# GaggiaBoard_V1.net
KiCad netlist of a schematic drawn in EAGLE
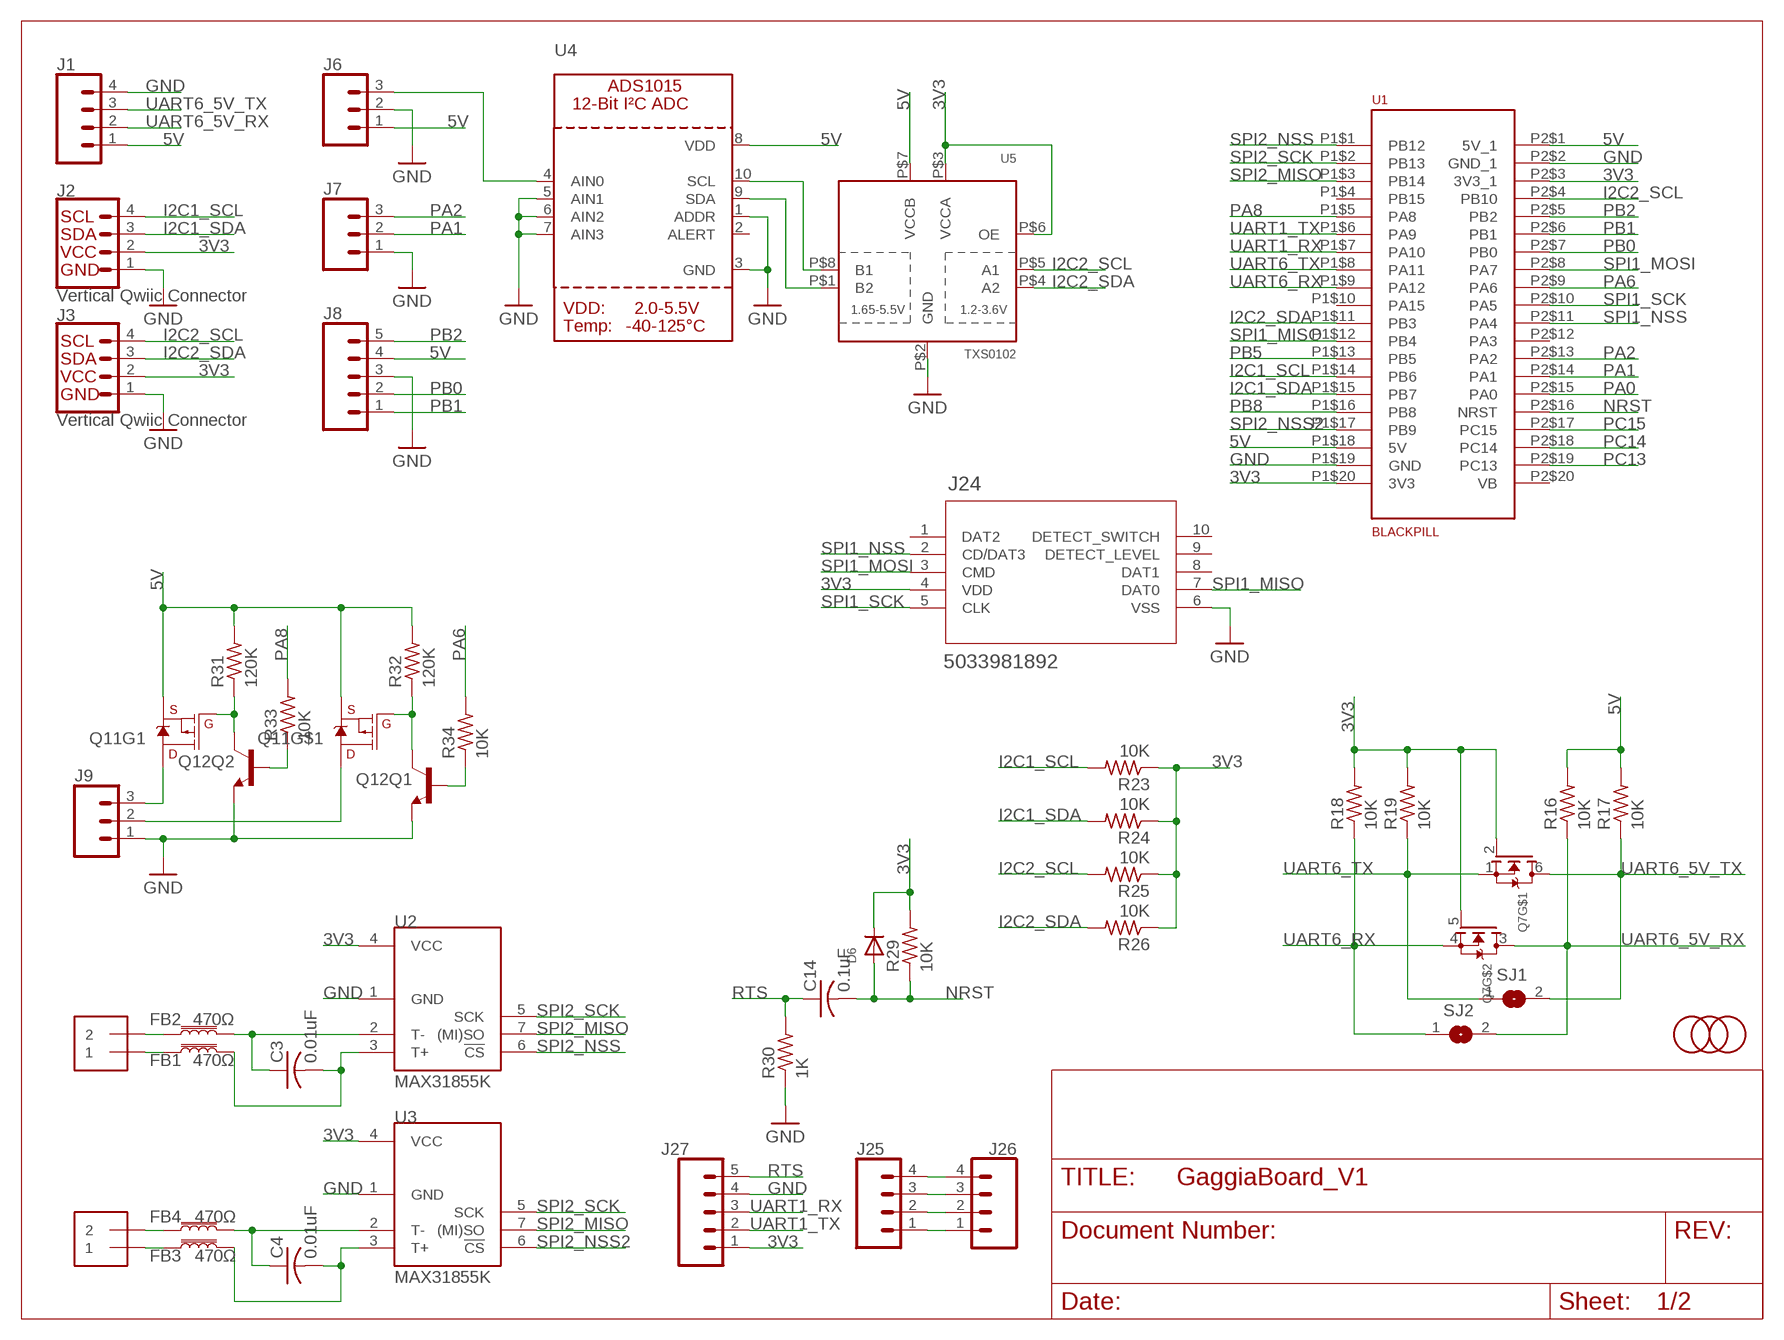
[diagram p0: schematic, sheet 1]
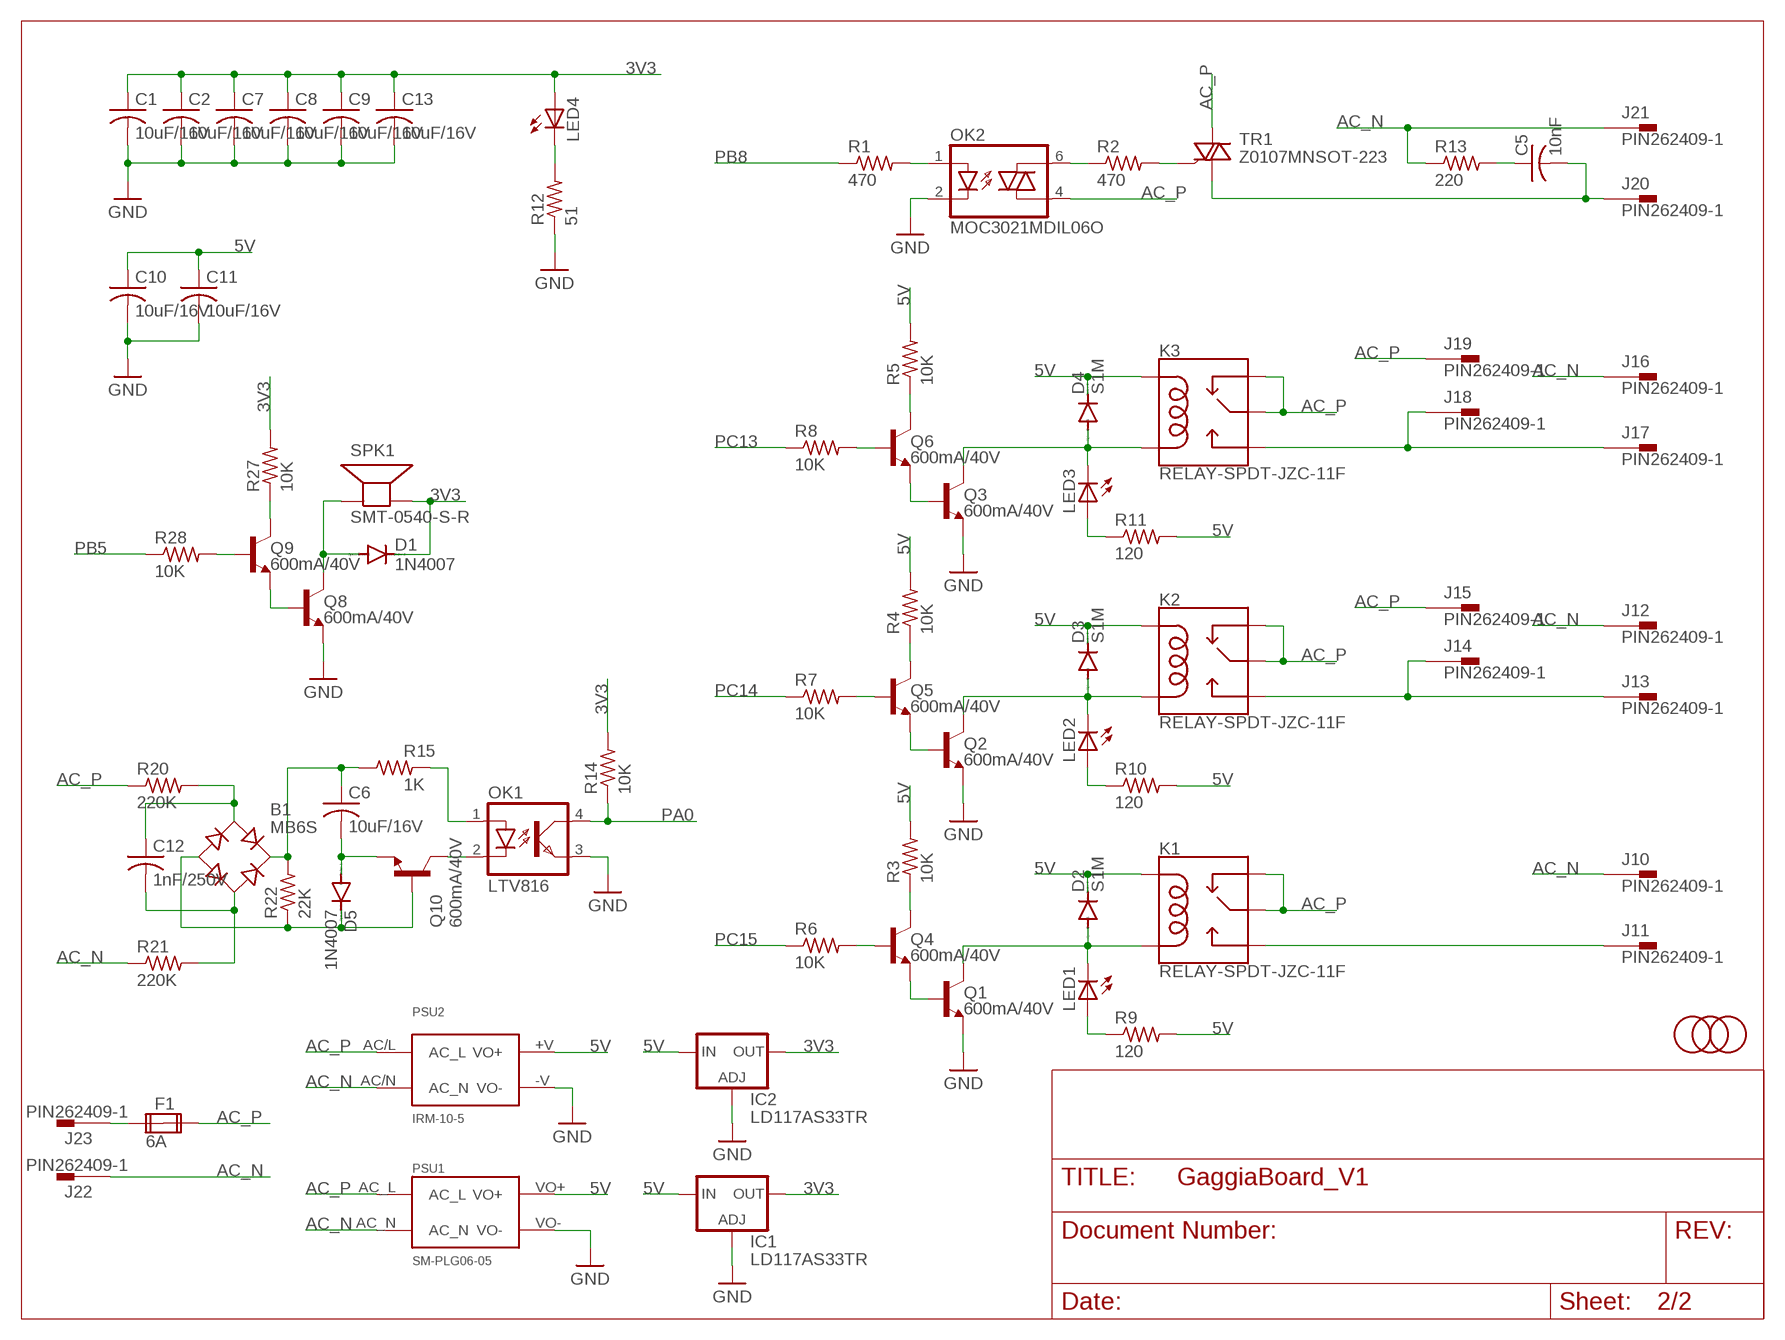
[diagram p1: schematic, sheet 2]

(export (version "E")
  (design (tool "Eeschema 10.0.6"))
  (components
    (comp (ref "B1")
      (value "MB6S")
      (footprint "eagle-import:SOIC-4")
      (libsource (lib "eagle-import") (part "MBS6"))
    )
    (comp (ref "C1")
      (value "10uF/16V")
      (footprint "eagle-import:C0603")
      (libsource (lib "eagle-import") (part "C-USC0603"))
    )
    (comp (ref "C2")
      (value "10uF/16V")
      (footprint "eagle-import:C0603")
      (libsource (lib "eagle-import") (part "C-USC0603"))
    )
    (comp (ref "C5")
      (value "10nF")
      (footprint "eagle-import:C1206")
      (libsource (lib "eagle-import") (part "C-USC1206"))
    )
    (comp (ref "C6")
      (value "10uF/16V")
      (footprint "eagle-import:C0603")
      (libsource (lib "eagle-import") (part "C-USC0603"))
    )
    (comp (ref "C7")
      (value "10uF/16V")
      (footprint "eagle-import:C0603")
      (libsource (lib "eagle-import") (part "C-USC0603"))
    )
    (comp (ref "C8")
      (value "10uF/16V")
      (footprint "eagle-import:C0603")
      (libsource (lib "eagle-import") (part "C-USC0603"))
    )
    (comp (ref "C9")
      (value "10uF/16V")
      (footprint "eagle-import:C0603")
      (libsource (lib "eagle-import") (part "C-USC0603"))
    )
    (comp (ref "C10")
      (value "10uF/16V")
      (footprint "eagle-import:C0603")
      (libsource (lib "eagle-import") (part "C-USC0603"))
    )
    (comp (ref "C11")
      (value "10uF/16V")
      (footprint "eagle-import:C0603")
      (libsource (lib "eagle-import") (part "C-USC0603"))
    )
    (comp (ref "C12")
      (value "1nF/250V")
      (footprint "eagle-import:C0603")
      (libsource (lib "eagle-import") (part "C-USC0603"))
    )
    (comp (ref "C13")
      (value "10uF/16V")
      (footprint "eagle-import:C0603")
      (libsource (lib "eagle-import") (part "C-USC0603"))
    )
    (comp (ref "D1")
      (value "1N4007")
      (footprint "eagle-import:DO214AC")
      (libsource (lib "eagle-import") (part "DIODE-DO214AC"))
    )
    (comp (ref "D2")
      (value "S1M")
      (footprint "eagle-import:SMA")
      (libsource (lib "eagle-import") (part "S1M"))
    )
    (comp (ref "D3")
      (value "S1M")
      (footprint "eagle-import:SMA")
      (libsource (lib "eagle-import") (part "S1M"))
    )
    (comp (ref "D4")
      (value "S1M")
      (footprint "eagle-import:SMA")
      (libsource (lib "eagle-import") (part "S1M"))
    )
    (comp (ref "D5")
      (value "1N4007")
      (footprint "eagle-import:DO214AC")
      (libsource (lib "eagle-import") (part "DIODE-DO214AC"))
    )
    (comp (ref "F1")
      (value "6A")
      (footprint "eagle-import:FUSE1")
      (libsource (lib "eagle-import") (part "FUSE2P"))
    )
    (comp (ref "IC1")
      (value "LD117AS33TR")
      (footprint "eagle-import:SOT223")
      (libsource (lib "eagle-import") (part "LD117A?S33TR"))
    )
    (comp (ref "IC2")
      (value "LD117AS33TR")
      (footprint "eagle-import:SOT223")
      (libsource (lib "eagle-import") (part "LD117A?S33TR"))
    )
    (comp (ref "J10")
      (value "PIN262409-1")
      (footprint "eagle-import:62409-1")
      (libsource (lib "eagle-import") (part "PIN262409-1"))
    )
    (comp (ref "J11")
      (value "PIN262409-1")
      (footprint "eagle-import:62409-1")
      (libsource (lib "eagle-import") (part "PIN262409-1"))
    )
    (comp (ref "J12")
      (value "PIN262409-1")
      (footprint "eagle-import:62409-1")
      (libsource (lib "eagle-import") (part "PIN262409-1"))
    )
    (comp (ref "J13")
      (value "PIN262409-1")
      (footprint "eagle-import:62409-1")
      (libsource (lib "eagle-import") (part "PIN262409-1"))
    )
    (comp (ref "J14")
      (value "PIN262409-1")
      (footprint "eagle-import:62409-1")
      (libsource (lib "eagle-import") (part "PIN262409-1"))
    )
    (comp (ref "J15")
      (value "PIN262409-1")
      (footprint "eagle-import:62409-1")
      (libsource (lib "eagle-import") (part "PIN262409-1"))
    )
    (comp (ref "J16")
      (value "PIN262409-1")
      (footprint "eagle-import:62409-1")
      (libsource (lib "eagle-import") (part "PIN262409-1"))
    )
    (comp (ref "J17")
      (value "PIN262409-1")
      (footprint "eagle-import:62409-1")
      (libsource (lib "eagle-import") (part "PIN262409-1"))
    )
    (comp (ref "J18")
      (value "PIN262409-1")
      (footprint "eagle-import:62409-1")
      (libsource (lib "eagle-import") (part "PIN262409-1"))
    )
    (comp (ref "J19")
      (value "PIN262409-1")
      (footprint "eagle-import:62409-1")
      (libsource (lib "eagle-import") (part "PIN262409-1"))
    )
    (comp (ref "J20")
      (value "PIN262409-1")
      (footprint "eagle-import:62409-1")
      (libsource (lib "eagle-import") (part "PIN262409-1"))
    )
    (comp (ref "J21")
      (value "PIN262409-1")
      (footprint "eagle-import:62409-1")
      (libsource (lib "eagle-import") (part "PIN262409-1"))
    )
    (comp (ref "J22")
      (value "PIN262409-1")
      (footprint "eagle-import:62409-1")
      (libsource (lib "eagle-import") (part "PIN262409-1"))
    )
    (comp (ref "J23")
      (value "PIN262409-1")
      (footprint "eagle-import:62409-1")
      (libsource (lib "eagle-import") (part "PIN262409-1"))
    )
    (comp (ref "K1")
      (value "RELAY-SPDT-JZC-11F")
      (footprint "eagle-import:RELAY-JZC")
      (libsource (lib "eagle-import") (part "RELAY-SPDT-JZC-11F"))
    )
    (comp (ref "K2")
      (value "RELAY-SPDT-JZC-11F")
      (footprint "eagle-import:RELAY-JZC")
      (libsource (lib "eagle-import") (part "RELAY-SPDT-JZC-11F"))
    )
    (comp (ref "K3")
      (value "RELAY-SPDT-JZC-11F")
      (footprint "eagle-import:RELAY-JZC")
      (libsource (lib "eagle-import") (part "RELAY-SPDT-JZC-11F"))
    )
    (comp (ref "LED1")
      (value "LEDCHIPLED_1206")
      (footprint "eagle-import:CHIPLED_1206")
      (libsource (lib "eagle-import") (part "LEDCHIPLED_1206"))
    )
    (comp (ref "LED2")
      (value "LEDCHIPLED_1206")
      (footprint "eagle-import:CHIPLED_1206")
      (libsource (lib "eagle-import") (part "LEDCHIPLED_1206"))
    )
    (comp (ref "LED3")
      (value "LEDCHIPLED_1206")
      (footprint "eagle-import:CHIPLED_1206")
      (libsource (lib "eagle-import") (part "LEDCHIPLED_1206"))
    )
    (comp (ref "LED4")
      (value "LEDCHIPLED_1206")
      (footprint "eagle-import:CHIPLED_1206")
      (libsource (lib "eagle-import") (part "LEDCHIPLED_1206"))
    )
    (comp (ref "MARK3")
      (value "FIDUCIAL")
      (footprint "eagle-import:FIDUCIAL_1MM")
      (libsource (lib "eagle-import") (part "FIDUCIAL"))
    )
    (comp (ref "MARK4")
      (value "FIDUCIAL")
      (footprint "eagle-import:FIDUCIAL_1MM")
      (libsource (lib "eagle-import") (part "FIDUCIAL"))
    )
    (comp (ref "MARK6")
      (value "FIDUCIAL")
      (footprint "eagle-import:FIDUCIAL_1MM")
      (libsource (lib "eagle-import") (part "FIDUCIAL"))
    )
    (comp (ref "OK1")
      (value "LTV816")
      (footprint "eagle-import:DIL04")
      (libsource (lib "eagle-import") (part "LTV816"))
    )
    (comp (ref "OK2")
      (value "MOC3021MDIL06O")
      (footprint "eagle-import:DIL06O")
      (libsource (lib "eagle-import") (part "MOC3021MDIL06O"))
    )
    (comp (ref "PSU1")
      (value "SM-PLG06-05")
      (footprint "eagle-import:SM-PLG06")
      (libsource (lib "eagle-import") (part "SM-PLG06-05"))
    )
    (comp (ref "PSU2")
      (value "IRM-10-5")
      (footprint "eagle-import:IRM-10")
      (libsource (lib "eagle-import") (part "IRM-10-5"))
    )
    (comp (ref "Q1")
      (value "600mA/40V")
      (footprint "eagle-import:SOT23-3")
      (libsource (lib "eagle-import") (part "TRANS_NPN-MMBT2222AL"))
    )
    (comp (ref "Q2")
      (value "600mA/40V")
      (footprint "eagle-import:SOT23-3")
      (libsource (lib "eagle-import") (part "TRANS_NPN-MMBT2222AL"))
    )
    (comp (ref "Q3")
      (value "600mA/40V")
      (footprint "eagle-import:SOT23-3")
      (libsource (lib "eagle-import") (part "TRANS_NPN-MMBT2222AL"))
    )
    (comp (ref "Q4")
      (value "600mA/40V")
      (footprint "eagle-import:SOT23-3")
      (libsource (lib "eagle-import") (part "TRANS_NPN-MMBT2222AL"))
    )
    (comp (ref "Q5")
      (value "600mA/40V")
      (footprint "eagle-import:SOT23-3")
      (libsource (lib "eagle-import") (part "TRANS_NPN-MMBT2222AL"))
    )
    (comp (ref "Q6")
      (value "600mA/40V")
      (footprint "eagle-import:SOT23-3")
      (libsource (lib "eagle-import") (part "TRANS_NPN-MMBT2222AL"))
    )
    (comp (ref "Q8")
      (value "600mA/40V")
      (footprint "eagle-import:SOT23-3")
      (libsource (lib "eagle-import") (part "TRANS_NPN-MMBT2222AL"))
    )
    (comp (ref "Q9")
      (value "600mA/40V")
      (footprint "eagle-import:SOT23-3")
      (libsource (lib "eagle-import") (part "TRANS_NPN-MMBT2222AL"))
    )
    (comp (ref "Q10")
      (value "600mA/40V")
      (footprint "eagle-import:SOT23-3")
      (libsource (lib "eagle-import") (part "TRANS_NPN-MMBT2222AL"))
    )
    (comp (ref "R1")
      (value "470")
      (footprint "eagle-import:R0603")
      (libsource (lib "eagle-import") (part "R-US_R0603"))
    )
    (comp (ref "R2")
      (value "470")
      (footprint "eagle-import:R0603")
      (libsource (lib "eagle-import") (part "R-US_R0603"))
    )
    (comp (ref "R3")
      (value "10K")
      (footprint "eagle-import:R0603")
      (libsource (lib "eagle-import") (part "R-US_R0603"))
    )
    (comp (ref "R4")
      (value "10K")
      (footprint "eagle-import:R0603")
      (libsource (lib "eagle-import") (part "R-US_R0603"))
    )
    (comp (ref "R5")
      (value "10K")
      (footprint "eagle-import:R0603")
      (libsource (lib "eagle-import") (part "R-US_R0603"))
    )
    (comp (ref "R6")
      (value "10K")
      (footprint "eagle-import:R0603")
      (libsource (lib "eagle-import") (part "R-US_R0603"))
    )
    (comp (ref "R7")
      (value "10K")
      (footprint "eagle-import:R0603")
      (libsource (lib "eagle-import") (part "R-US_R0603"))
    )
    (comp (ref "R8")
      (value "10K")
      (footprint "eagle-import:R0603")
      (libsource (lib "eagle-import") (part "R-US_R0603"))
    )
    (comp (ref "R9")
      (value "120")
      (footprint "eagle-import:R0603")
      (libsource (lib "eagle-import") (part "R-US_R0603"))
    )
    (comp (ref "R10")
      (value "120")
      (footprint "eagle-import:R0603")
      (libsource (lib "eagle-import") (part "R-US_R0603"))
    )
    (comp (ref "R11")
      (value "120")
      (footprint "eagle-import:R0603")
      (libsource (lib "eagle-import") (part "R-US_R0603"))
    )
    (comp (ref "R12")
      (value "51")
      (footprint "eagle-import:R0603")
      (libsource (lib "eagle-import") (part "R-US_R0603"))
    )
    (comp (ref "R13")
      (value "220")
      (footprint "eagle-import:R2512")
      (libsource (lib "eagle-import") (part "R-US_R2512"))
    )
    (comp (ref "R14")
      (value "10K")
      (footprint "eagle-import:R0603")
      (libsource (lib "eagle-import") (part "R-US_R0603"))
    )
    (comp (ref "R15")
      (value "1K")
      (footprint "eagle-import:R0603")
      (libsource (lib "eagle-import") (part "R-US_R0603"))
    )
    (comp (ref "R20")
      (value "220K")
      (footprint "eagle-import:R1206")
      (libsource (lib "eagle-import") (part "R-US_R1206"))
    )
    (comp (ref "R21")
      (value "220K")
      (footprint "eagle-import:R1206")
      (libsource (lib "eagle-import") (part "R-US_R1206"))
    )
    (comp (ref "R22")
      (value "22K")
      (footprint "eagle-import:R0603")
      (libsource (lib "eagle-import") (part "R-US_R0603"))
    )
    (comp (ref "R27")
      (value "10K")
      (footprint "eagle-import:R0603")
      (libsource (lib "eagle-import") (part "R-US_R0603"))
    )
    (comp (ref "R28")
      (value "10K")
      (footprint "eagle-import:R0603")
      (libsource (lib "eagle-import") (part "R-US_R0603"))
    )
    (comp (ref "SPK1")
      (value "SMT-0540-S-R")
      (footprint "eagle-import:SMT-0540-S-R")
      (libsource (lib "eagle-import") (part "SMT-0540-S-R"))
    )
    (comp (ref "TR1")
      (value "Z0107MNSOT-223")
      (footprint "eagle-import:SOT223")
      (libsource (lib "eagle-import") (part "Z0107MNSOT-223"))
    )
    (comp (ref "C3")
      (value "0.01uF")
      (footprint "eagle-import:C0603")
      (libsource (lib "eagle-import") (part "C-USC0603"))
    )
    (comp (ref "C4")
      (value "0.01uF")
      (footprint "eagle-import:C0603")
      (libsource (lib "eagle-import") (part "C-USC0603"))
    )
    (comp (ref "C14")
      (value "0.1uF")
      (footprint "eagle-import:C0603")
      (libsource (lib "eagle-import") (part "C-USC0603"))
    )
    (comp (ref "D6")
      (value "DIODESOD-123")
      (footprint "eagle-import:SOD-123")
      (libsource (lib "eagle-import") (part "DIODESOD-123"))
    )
    (comp (ref "FB1")
      (value "470Ω")
      (footprint "eagle-import:0603")
      (libsource (lib "eagle-import") (part "FERRITE_BEAD-0603-470Ω-100MHZ-1A-200MILIΩ"))
    )
    (comp (ref "FB2")
      (value "470Ω")
      (footprint "eagle-import:0603")
      (libsource (lib "eagle-import") (part "FERRITE_BEAD-0603-470Ω-100MHZ-1A-200MILIΩ"))
    )
    (comp (ref "FB3")
      (value "470Ω")
      (footprint "eagle-import:0603")
      (libsource (lib "eagle-import") (part "FERRITE_BEAD-0603-470Ω-100MHZ-1A-200MILIΩ"))
    )
    (comp (ref "FB4")
      (value "470Ω")
      (footprint "eagle-import:0603")
      (libsource (lib "eagle-import") (part "FERRITE_BEAD-0603-470Ω-100MHZ-1A-200MILIΩ"))
    )
    (comp (ref "J1")
      (value "CONN_04POLAR")
      (footprint "eagle-import:MOLEX-1X4")
      (libsource (lib "eagle-import") (part "CONN_04POLAR"))
    )
    (comp (ref "J2")
      (value "Vertical Qwiic Connector")
      (footprint "eagle-import:JST04_1MM_VERT")
      (libsource (lib "eagle-import") (part "QWIIC_CONNECTOR"))
    )
    (comp (ref "J3")
      (value "Vertical Qwiic Connector")
      (footprint "eagle-import:JST04_1MM_VERT")
      (libsource (lib "eagle-import") (part "QWIIC_CONNECTOR"))
    )
    (comp (ref "J4")
      (value "1X2-3.5MM")
      (footprint "eagle-import:1X2-3.5MM")
      (libsource (lib "eagle-import") (part "1X2-3.5MM"))
    )
    (comp (ref "J5")
      (value "1X2-3.5MM")
      (footprint "eagle-import:1X2-3.5MM")
      (libsource (lib "eagle-import") (part "1X2-3.5MM"))
    )
    (comp (ref "J6")
      (value "CONN_03JST-PTH-VERT")
      (footprint "eagle-import:JST-3-PTH-VERT")
      (libsource (lib "eagle-import") (part "CONN_03JST-PTH-VERT"))
    )
    (comp (ref "J7")
      (value "CONN_03JST-PTH-VERT")
      (footprint "eagle-import:JST-3-PTH-VERT")
      (libsource (lib "eagle-import") (part "CONN_03JST-PTH-VERT"))
    )
    (comp (ref "J8")
      (value "CONN_05JST-VERT")
      (footprint "eagle-import:JST-5-PTH-VERT")
      (libsource (lib "eagle-import") (part "CONN_05JST-VERT"))
    )
    (comp (ref "J9")
      (value "CONN_03JST-PTH-VERT")
      (footprint "eagle-import:JST-3-PTH-VERT")
      (libsource (lib "eagle-import") (part "CONN_03JST-PTH-VERT"))
    )
    (comp (ref "J24")
      (value "5033981892")
      (footprint "eagle-import:503398-1892_MOL")
      (fields (field (name "COPYRIGHT") "Copyright (C) 2022 Ultra Librarian. All rights reserved."))
      (libsource (lib "eagle-import") (part "5033981892"))
    )
    (comp (ref "J25")
      (value "CONN_041X04_NO_SILK")
      (footprint "eagle-import:1X04_NO_SILK")
      (libsource (lib "eagle-import") (part "CONN_041X04_NO_SILK"))
    )
    (comp (ref "J26")
      (value "CONN_041X04_NO_SILK")
      (footprint "eagle-import:1X04_NO_SILK")
      (libsource (lib "eagle-import") (part "CONN_041X04_NO_SILK"))
    )
    (comp (ref "J27")
      (value "CONN_05NO_SILK")
      (footprint "eagle-import:1X05_NO_SILK")
      (libsource (lib "eagle-import") (part "CONN_05NO_SILK"))
    )
    (comp (ref "MARK1")
      (value "FIDUCIAL")
      (footprint "eagle-import:FIDUCIAL_1MM")
      (libsource (lib "eagle-import") (part "FIDUCIAL"))
    )
    (comp (ref "MARK2")
      (value "FIDUCIAL")
      (footprint "eagle-import:FIDUCIAL_1MM")
      (libsource (lib "eagle-import") (part "FIDUCIAL"))
    )
    (comp (ref "MARK5")
      (value "FIDUCIAL")
      (footprint "eagle-import:FIDUCIAL_1MM")
      (libsource (lib "eagle-import") (part "FIDUCIAL"))
    )
    (comp (ref "Q7")
      (value "MOSFET-N_DUAL")
      (footprint "eagle-import:SOT363")
      (fields (field (name "LCSC") "C150488"))
      (libsource (lib "eagle-import") (part "MOSFET-N_DUAL"))
    )
    (comp (ref "Q11")
      (value "MOSFET_PCH_DUAL-DMP2240UDM")
      (footprint "eagle-import:SOT26")
      (fields (field (name "LCSC") "C397948"))
      (libsource (lib "eagle-import") (part "MOSFET_PCH_DUAL-DMP2240UDM"))
    )
    (comp (ref "Q12")
      (value "TRANS_NPN_DUAL-MBT3904DW1T1")
      (footprint "eagle-import:SC70-6")
      (fields (field (name "LCSC") "C896759"))
      (libsource (lib "eagle-import") (part "TRANS_NPN_DUAL-MBT3904DW1T1"))
    )
    (comp (ref "R16")
      (value "10K")
      (footprint "eagle-import:R0603")
      (libsource (lib "eagle-import") (part "R-US_R0603"))
    )
    (comp (ref "R17")
      (value "10K")
      (footprint "eagle-import:R0603")
      (libsource (lib "eagle-import") (part "R-US_R0603"))
    )
    (comp (ref "R18")
      (value "10K")
      (footprint "eagle-import:R0603")
      (libsource (lib "eagle-import") (part "R-US_R0603"))
    )
    (comp (ref "R19")
      (value "10K")
      (footprint "eagle-import:R0603")
      (libsource (lib "eagle-import") (part "R-US_R0603"))
    )
    (comp (ref "R23")
      (value "10K")
      (footprint "eagle-import:R0603")
      (libsource (lib "eagle-import") (part "R-US_R0603"))
    )
    (comp (ref "R24")
      (value "10K")
      (footprint "eagle-import:R0603")
      (libsource (lib "eagle-import") (part "R-US_R0603"))
    )
    (comp (ref "R25")
      (value "10K")
      (footprint "eagle-import:R0603")
      (libsource (lib "eagle-import") (part "R-US_R0603"))
    )
    (comp (ref "R26")
      (value "10K")
      (footprint "eagle-import:R0603")
      (libsource (lib "eagle-import") (part "R-US_R0603"))
    )
    (comp (ref "R29")
      (value "10K")
      (footprint "eagle-import:R0603")
      (libsource (lib "eagle-import") (part "R-US_R0603"))
    )
    (comp (ref "R30")
      (value "1K")
      (footprint "eagle-import:R0603")
      (libsource (lib "eagle-import") (part "R-US_R0603"))
    )
    (comp (ref "R31")
      (value "120K")
      (footprint "eagle-import:R0603")
      (libsource (lib "eagle-import") (part "R-US_R0603"))
    )
    (comp (ref "R32")
      (value "120K")
      (footprint "eagle-import:R0603")
      (libsource (lib "eagle-import") (part "R-US_R0603"))
    )
    (comp (ref "R33")
      (value "10K")
      (footprint "eagle-import:R0603")
      (libsource (lib "eagle-import") (part "R-US_R0603"))
    )
    (comp (ref "R34")
      (value "10K")
      (footprint "eagle-import:R0603")
      (libsource (lib "eagle-import") (part "R-US_R0603"))
    )
    (comp (ref "SJ1")
      (value "SOLDERJUMPER")
      (footprint "eagle-import:SOLDERJUMPER_ARROW_NOPASTE")
      (libsource (lib "eagle-import") (part "SOLDERJUMPER"))
    )
    (comp (ref "SJ2")
      (value "SOLDERJUMPER")
      (footprint "eagle-import:SOLDERJUMPER_ARROW_NOPASTE")
      (libsource (lib "eagle-import") (part "SOLDERJUMPER"))
    )
    (comp (ref "U1")
      (value "BLACKPILL")
      (footprint "eagle-import:BLACKPILL")
      (libsource (lib "eagle-import") (part "BLACKPILL"))
    )
    (comp (ref "U2")
      (value "MAX31855K")
      (footprint "eagle-import:SO08")
      (libsource (lib "eagle-import") (part "MAX31855K"))
    )
    (comp (ref "U3")
      (value "MAX31855K")
      (footprint "eagle-import:SO08")
      (libsource (lib "eagle-import") (part "MAX31855K"))
    )
    (comp (ref "U4")
      (value "ADC_ADS1015")
      (footprint "eagle-import:MSOP10")
      (libsource (lib "eagle-import") (part "ADC_ADS1015"))
    )
    (comp (ref "U5")
      (value "TXS0102")
      (footprint "eagle-import:VFSOP-8")
      (libsource (lib "eagle-import") (part "TXS0102"))
    )
  )
  (nets
    (net (code "1") (name "3V3") (class "Default")
      (node (ref "C1") (pin "1") (pinfunction "1_1") (pintype "passive"))
      (node (ref "C13") (pin "1") (pinfunction "1_1") (pintype "passive"))
      (node (ref "C2") (pin "1") (pinfunction "1_1") (pintype "passive"))
      (node (ref "C7") (pin "1") (pinfunction "1_1") (pintype "passive"))
      (node (ref "C8") (pin "1") (pinfunction "1_1") (pintype "passive"))
      (node (ref "C9") (pin "1") (pinfunction "1_1") (pintype "passive"))
      (node (ref "D1") (pin "C") (pinfunction "C_C") (pintype "passive"))
      (node (ref "D6") (pin "C") (pinfunction "C_C") (pintype "passive"))
      (node (ref "IC1") (pin "4") (pinfunction "OUT_4") (pintype "passive"))
      (node (ref "IC2") (pin "4") (pinfunction "OUT_4") (pintype "passive"))
      (node (ref "J2") (pin "2") (pinfunction "2_2") (pintype "power_in"))
      (node (ref "J24") (pin "4") (pinfunction "VDD_4") (pintype "power_in"))
      (node (ref "J25") (pin "1") (pinfunction "1_1") (pintype "passive"))
      (node (ref "J26") (pin "1") (pinfunction "1_1") (pintype "passive"))
      (node (ref "J27") (pin "1") (pinfunction "1_1") (pintype "passive"))
      (node (ref "J3") (pin "2") (pinfunction "2_2") (pintype "power_in"))
      (node (ref "LED4") (pin "A") (pinfunction "A_A") (pintype "passive"))
      (node (ref "Q7") (pin "2") (pinfunction "G_2") (pintype "bidirectional"))
      (node (ref "Q7") (pin "5") (pinfunction "G_5") (pintype "bidirectional"))
      (node (ref "R14") (pin "2") (pinfunction "2_2") (pintype "passive"))
      (node (ref "R18") (pin "2") (pinfunction "2_2") (pintype "passive"))
      (node (ref "R19") (pin "2") (pinfunction "2_2") (pintype "passive"))
      (node (ref "R23") (pin "1") (pinfunction "1_1") (pintype "passive"))
      (node (ref "R24") (pin "1") (pinfunction "1_1") (pintype "passive"))
      (node (ref "R25") (pin "1") (pinfunction "1_1") (pintype "passive"))
      (node (ref "R26") (pin "1") (pinfunction "1_1") (pintype "passive"))
      (node (ref "R27") (pin "2") (pinfunction "2_2") (pintype "passive"))
      (node (ref "R29") (pin "2") (pinfunction "2_2") (pintype "passive"))
      (node (ref "SPK1") (pin "+") (pinfunction "-_+") (pintype "passive"))
      (node (ref "U1") (pin "P1$20") (pinfunction "3V3_P1$20") (pintype "power_in"))
      (node (ref "U1") (pin "P2$3") (pinfunction "3V3_1_P2$3") (pintype "power_in"))
      (node (ref "U2") (pin "4") (pinfunction "VCC_4") (pintype "bidirectional"))
      (node (ref "U3") (pin "4") (pinfunction "VCC_4") (pintype "bidirectional"))
      (node (ref "U5") (pin "P$3") (pinfunction "VCCA_P$3") (pintype "bidirectional"))
      (node (ref "U5") (pin "P$6") (pinfunction "OE_P$6") (pintype "bidirectional"))
    )
    (net (code "2") (name "5V") (class "Default")
      (node (ref "C10") (pin "1") (pinfunction "1_1") (pintype "passive"))
      (node (ref "C11") (pin "1") (pinfunction "1_1") (pintype "passive"))
      (node (ref "D2") (pin "C") (pinfunction "C_C") (pintype "passive"))
      (node (ref "D3") (pin "C") (pinfunction "C_C") (pintype "passive"))
      (node (ref "D4") (pin "C") (pinfunction "C_C") (pintype "passive"))
      (node (ref "IC1") (pin "3") (pinfunction "IN_3") (pintype "input"))
      (node (ref "IC2") (pin "3") (pinfunction "IN_3") (pintype "input"))
      (node (ref "J1") (pin "1") (pinfunction "1_1") (pintype "passive"))
      (node (ref "J6") (pin "1") (pinfunction "1_1") (pintype "passive"))
      (node (ref "J8") (pin "4") (pinfunction "4_4") (pintype "passive"))
      (node (ref "K1") (pin "5") (pinfunction "COIL1_5") (pintype "bidirectional"))
      (node (ref "K2") (pin "5") (pinfunction "COIL1_5") (pintype "bidirectional"))
      (node (ref "K3") (pin "5") (pinfunction "COIL1_5") (pintype "bidirectional"))
      (node (ref "PSU1") (pin "VO+") (pinfunction "VO+_VO+") (pintype "bidirectional"))
      (node (ref "PSU2") (pin "+V") (pinfunction "VO+_+V") (pintype "bidirectional"))
      (node (ref "Q11") (pin "S1") (pinfunction "S_S1") (pintype "bidirectional"))
      (node (ref "Q11") (pin "S2") (pinfunction "S_S2") (pintype "bidirectional"))
      (node (ref "R10") (pin "2") (pinfunction "2_2") (pintype "passive"))
      (node (ref "R11") (pin "2") (pinfunction "2_2") (pintype "passive"))
      (node (ref "R16") (pin "2") (pinfunction "2_2") (pintype "passive"))
      (node (ref "R17") (pin "2") (pinfunction "2_2") (pintype "passive"))
      (node (ref "R3") (pin "2") (pinfunction "2_2") (pintype "passive"))
      (node (ref "R31") (pin "2") (pinfunction "2_2") (pintype "passive"))
      (node (ref "R32") (pin "2") (pinfunction "2_2") (pintype "passive"))
      (node (ref "R4") (pin "2") (pinfunction "2_2") (pintype "passive"))
      (node (ref "R5") (pin "2") (pinfunction "2_2") (pintype "passive"))
      (node (ref "R9") (pin "2") (pinfunction "2_2") (pintype "passive"))
      (node (ref "U1") (pin "P1$18") (pinfunction "5V_P1$18") (pintype "power_in"))
      (node (ref "U1") (pin "P2$1") (pinfunction "5V_1_P2$1") (pintype "power_in"))
      (node (ref "U4") (pin "8") (pinfunction "VDD_8") (pintype "bidirectional"))
      (node (ref "U5") (pin "P$7") (pinfunction "VCCB_P$7") (pintype "bidirectional"))
    )
    (net (code "3") (name "AC_N") (class "Default")
      (node (ref "J10") (pin "A1") (pinfunction "1_A1") (pintype "passive"))
      (node (ref "J10") (pin "A2") (pinfunction "1_A2") (pintype "passive"))
      (node (ref "J12") (pin "A1") (pinfunction "1_A1") (pintype "passive"))
      (node (ref "J12") (pin "A2") (pinfunction "1_A2") (pintype "passive"))
      (node (ref "J16") (pin "A1") (pinfunction "1_A1") (pintype "passive"))
      (node (ref "J16") (pin "A2") (pinfunction "1_A2") (pintype "passive"))
      (node (ref "J21") (pin "A1") (pinfunction "1_A1") (pintype "passive"))
      (node (ref "J21") (pin "A2") (pinfunction "1_A2") (pintype "passive"))
      (node (ref "J22") (pin "A1") (pinfunction "1_A1") (pintype "passive"))
      (node (ref "J22") (pin "A2") (pinfunction "1_A2") (pintype "passive"))
      (node (ref "PSU1") (pin "AC_N") (pinfunction "AC_N_AC_N") (pintype "bidirectional"))
      (node (ref "PSU2") (pin "AC/N") (pinfunction "AC_N_AC/N") (pintype "bidirectional"))
      (node (ref "R13") (pin "1") (pinfunction "1_1") (pintype "passive"))
      (node (ref "R21") (pin "1") (pinfunction "1_1") (pintype "passive"))
    )
    (net (code "4") (name "AC_P") (class "Default")
      (node (ref "F1") (pin "2A") (pinfunction "2A_2A") (pintype "passive"))
      (node (ref "J15") (pin "A1") (pinfunction "1_A1") (pintype "passive"))
      (node (ref "J15") (pin "A2") (pinfunction "1_A2") (pintype "passive"))
      (node (ref "J19") (pin "A1") (pinfunction "1_A1") (pintype "passive"))
      (node (ref "J19") (pin "A2") (pinfunction "1_A2") (pintype "passive"))
      (node (ref "K1") (pin "2") (pinfunction "NC_2") (pintype "bidirectional"))
      (node (ref "K1") (pin "4") (pinfunction "MAIN_4") (pintype "bidirectional"))
      (node (ref "K2") (pin "2") (pinfunction "NC_2") (pintype "bidirectional"))
      (node (ref "K2") (pin "4") (pinfunction "MAIN_4") (pintype "bidirectional"))
      (node (ref "K3") (pin "2") (pinfunction "NC_2") (pintype "bidirectional"))
      (node (ref "K3") (pin "4") (pinfunction "MAIN_4") (pintype "bidirectional"))
      (node (ref "OK2") (pin "4") (pinfunction "A1_4") (pintype "passive"))
      (node (ref "PSU1") (pin "AC_L") (pinfunction "AC_L_AC_L") (pintype "bidirectional"))
      (node (ref "PSU2") (pin "AC/L") (pinfunction "AC_L_AC/L") (pintype "bidirectional"))
      (node (ref "R20") (pin "1") (pinfunction "1_1") (pintype "passive"))
      (node (ref "TR1") (pin "2") (pinfunction "A2_2") (pintype "passive"))
      (node (ref "TR1") (pin "4") (pinfunction "A2_4") (pintype "passive"))
    )
    (net (code "5") (name "GND") (class "Default")
      (node (ref "C1") (pin "2") (pinfunction "2_2") (pintype "passive"))
      (node (ref "C10") (pin "2") (pinfunction "2_2") (pintype "passive"))
      (node (ref "C11") (pin "2") (pinfunction "2_2") (pintype "passive"))
      (node (ref "C13") (pin "2") (pinfunction "2_2") (pintype "passive"))
      (node (ref "C2") (pin "2") (pinfunction "2_2") (pintype "passive"))
      (node (ref "C7") (pin "2") (pinfunction "2_2") (pintype "passive"))
      (node (ref "C8") (pin "2") (pinfunction "2_2") (pintype "passive"))
      (node (ref "C9") (pin "2") (pinfunction "2_2") (pintype "passive"))
      (node (ref "IC1") (pin "1") (pinfunction "ADJ_1") (pintype "input"))
      (node (ref "IC2") (pin "1") (pinfunction "ADJ_1") (pintype "input"))
      (node (ref "J1") (pin "4") (pinfunction "4_4") (pintype "passive"))
      (node (ref "J2") (pin "1") (pinfunction "1_1") (pintype "power_in"))
      (node (ref "J24") (pin "6") (pinfunction "VSS_6") (pintype "passive"))
      (node (ref "J25") (pin "4") (pinfunction "4_4") (pintype "passive"))
      (node (ref "J26") (pin "4") (pinfunction "4_4") (pintype "passive"))
      (node (ref "J27") (pin "4") (pinfunction "4_4") (pintype "passive"))
      (node (ref "J3") (pin "1") (pinfunction "1_1") (pintype "power_in"))
      (node (ref "J6") (pin "2") (pinfunction "2_2") (pintype "passive"))
      (node (ref "J7") (pin "1") (pinfunction "1_1") (pintype "passive"))
      (node (ref "J8") (pin "3") (pinfunction "3_3") (pintype "passive"))
      (node (ref "J9") (pin "1") (pinfunction "1_1") (pintype "passive"))
      (node (ref "OK1") (pin "3") (pinfunction "EMIT_3") (pintype "passive"))
      (node (ref "OK2") (pin "2") (pinfunction "C_2") (pintype "passive"))
      (node (ref "PSU1") (pin "VO-") (pinfunction "VO-_VO-") (pintype "bidirectional"))
      (node (ref "PSU2") (pin "-V") (pinfunction "VO-_-V") (pintype "bidirectional"))
      (node (ref "Q1") (pin "2") (pinfunction "E_2") (pintype "passive"))
      (node (ref "Q12") (pin "1") (pinfunction "E_1") (pintype "passive"))
      (node (ref "Q12") (pin "4") (pinfunction "E_4") (pintype "passive"))
      (node (ref "Q2") (pin "2") (pinfunction "E_2") (pintype "passive"))
      (node (ref "Q3") (pin "2") (pinfunction "E_2") (pintype "passive"))
      (node (ref "Q8") (pin "2") (pinfunction "E_2") (pintype "passive"))
      (node (ref "R12") (pin "1") (pinfunction "1_1") (pintype "passive"))
      (node (ref "R30") (pin "1") (pinfunction "1_1") (pintype "passive"))
      (node (ref "U1") (pin "P1$19") (pinfunction "GND_P1$19") (pintype "power_in"))
      (node (ref "U1") (pin "P2$2") (pinfunction "GND_1_P2$2") (pintype "power_in"))
      (node (ref "U2") (pin "1") (pinfunction "GND_1") (pintype "bidirectional"))
      (node (ref "U3") (pin "1") (pinfunction "GND_1") (pintype "bidirectional"))
      (node (ref "U4") (pin "1") (pinfunction "ADDR_1") (pintype "bidirectional"))
      (node (ref "U4") (pin "3") (pinfunction "GND_3") (pintype "bidirectional"))
      (node (ref "U4") (pin "5") (pinfunction "AIN1_5") (pintype "bidirectional"))
      (node (ref "U4") (pin "6") (pinfunction "AIN2_6") (pintype "bidirectional"))
      (node (ref "U4") (pin "7") (pinfunction "AIN3_7") (pintype "bidirectional"))
      (node (ref "U5") (pin "P$2") (pinfunction "GND_P$2") (pintype "bidirectional"))
    )
    (net (code "6") (name "I2C1_SCL") (class "Default")
      (node (ref "J2") (pin "4") (pinfunction "4_4") (pintype "passive"))
      (node (ref "R23") (pin "2") (pinfunction "2_2") (pintype "passive"))
      (node (ref "U1") (pin "P1$14") (pinfunction "PB6_P1$14") (pintype "bidirectional"))
    )
    (net (code "7") (name "I2C1_SDA") (class "Default")
      (node (ref "J2") (pin "3") (pinfunction "3_3") (pintype "passive"))
      (node (ref "R24") (pin "2") (pinfunction "2_2") (pintype "passive"))
      (node (ref "U1") (pin "P1$15") (pinfunction "PB7_P1$15") (pintype "bidirectional"))
    )
    (net (code "8") (name "I2C2_SCL") (class "Default")
      (node (ref "J3") (pin "4") (pinfunction "4_4") (pintype "passive"))
      (node (ref "R25") (pin "2") (pinfunction "2_2") (pintype "passive"))
      (node (ref "U1") (pin "P2$4") (pinfunction "PB10_P2$4") (pintype "bidirectional"))
      (node (ref "U5") (pin "P$5") (pinfunction "A1_P$5") (pintype "bidirectional"))
    )
    (net (code "9") (name "I2C2_SDA") (class "Default")
      (node (ref "J3") (pin "3") (pinfunction "3_3") (pintype "passive"))
      (node (ref "R26") (pin "2") (pinfunction "2_2") (pintype "passive"))
      (node (ref "U1") (pin "P1$11") (pinfunction "PB3_P1$11") (pintype "bidirectional"))
      (node (ref "U5") (pin "P$4") (pinfunction "A2_P$4") (pintype "bidirectional"))
    )
    (net (code "10") (name "NRST") (class "Default")
      (node (ref "C14") (pin "2") (pinfunction "2_2") (pintype "passive"))
      (node (ref "D6") (pin "A") (pinfunction "A_A") (pintype "passive"))
      (node (ref "R29") (pin "1") (pinfunction "1_1") (pintype "passive"))
      (node (ref "U1") (pin "P2$16") (pinfunction "NRST_P2$16") (pintype "bidirectional"))
    )
    (net (code "11") (name "Net-(B1-AC1)") (class "Default")
      (node (ref "B1") (pin "~1") (pinfunction "AC1_~1") (pintype "passive"))
      (node (ref "C12") (pin "2") (pinfunction "2_2") (pintype "passive"))
      (node (ref "R21") (pin "2") (pinfunction "2_2") (pintype "passive"))
    )
    (net (code "12") (name "Net-(B1-AC2)") (class "Default")
      (node (ref "B1") (pin "~2") (pinfunction "AC2_~2") (pintype "passive"))
      (node (ref "C12") (pin "1") (pinfunction "1_1") (pintype "passive"))
      (node (ref "R20") (pin "2") (pinfunction "2_2") (pintype "passive"))
    )
    (net (code "13") (name "Net-(B1-Pad+)") (class "Default")
      (node (ref "B1") (pin "+") (pinfunction "+_+") (pintype "passive"))
      (node (ref "C6") (pin "1") (pinfunction "1_1") (pintype "passive"))
      (node (ref "R15") (pin "1") (pinfunction "1_1") (pintype "passive"))
      (node (ref "R22") (pin "2") (pinfunction "2_2") (pintype "passive"))
    )
    (net (code "14") (name "Net-(C5-Pad1)") (class "Default")
      (node (ref "C5") (pin "1") (pinfunction "1_1") (pintype "passive"))
      (node (ref "R13") (pin "2") (pinfunction "2_2") (pintype "passive"))
    )
    (net (code "15") (name "Net-(F1-Pad1A)") (class "Default")
      (node (ref "F1") (pin "1A") (pinfunction "1A_1A") (pintype "passive"))
      (node (ref "J23") (pin "A1") (pinfunction "1_A1") (pintype "passive"))
      (node (ref "J23") (pin "A2") (pinfunction "1_A2") (pintype "passive"))
    )
    (net (code "16") (name "Net-(FB1-Pad1)") (class "Default")
      (node (ref "FB1") (pin "1") (pinfunction "1_1") (pintype "passive"))
      (node (ref "J4") (pin "1") (pinfunction "1_1") (pintype "passive"))
    )
    (net (code "17") (name "Net-(FB2-Pad1)") (class "Default")
      (node (ref "FB2") (pin "1") (pinfunction "1_1") (pintype "passive"))
      (node (ref "J4") (pin "2") (pinfunction "2_2") (pintype "passive"))
    )
    (net (code "18") (name "Net-(FB3-Pad1)") (class "Default")
      (node (ref "FB3") (pin "1") (pinfunction "1_1") (pintype "passive"))
      (node (ref "J5") (pin "1") (pinfunction "1_1") (pintype "passive"))
    )
    (net (code "19") (name "Net-(FB4-Pad1)") (class "Default")
      (node (ref "FB4") (pin "1") (pinfunction "1_1") (pintype "passive"))
      (node (ref "J5") (pin "2") (pinfunction "2_2") (pintype "passive"))
    )
    (net (code "20") (name "Net-(J25-Pad2)") (class "Default")
      (node (ref "J25") (pin "2") (pinfunction "2_2") (pintype "passive"))
      (node (ref "J26") (pin "2") (pinfunction "2_2") (pintype "passive"))
    )
    (net (code "21") (name "Net-(J25-Pad3)") (class "Default")
      (node (ref "J25") (pin "3") (pinfunction "3_3") (pintype "passive"))
      (node (ref "J26") (pin "3") (pinfunction "3_3") (pintype "passive"))
    )
    (net (code "22") (name "Net-(K1-COIL2)") (class "Default")
      (node (ref "D2") (pin "A") (pinfunction "A_A") (pintype "passive"))
      (node (ref "K1") (pin "1") (pinfunction "COIL2_1") (pintype "bidirectional"))
      (node (ref "LED1") (pin "C") (pinfunction "C_C") (pintype "passive"))
      (node (ref "Q1") (pin "3") (pinfunction "C_3") (pintype "passive"))
    )
    (net (code "23") (name "Net-(K1-NO)") (class "Default")
      (node (ref "J11") (pin "A1") (pinfunction "1_A1") (pintype "passive"))
      (node (ref "J11") (pin "A2") (pinfunction "1_A2") (pintype "passive"))
      (node (ref "K1") (pin "3") (pinfunction "NO_3") (pintype "bidirectional"))
    )
    (net (code "24") (name "Net-(K2-COIL2)") (class "Default")
      (node (ref "D3") (pin "A") (pinfunction "A_A") (pintype "passive"))
      (node (ref "K2") (pin "1") (pinfunction "COIL2_1") (pintype "bidirectional"))
      (node (ref "LED2") (pin "C") (pinfunction "C_C") (pintype "passive"))
      (node (ref "Q2") (pin "3") (pinfunction "C_3") (pintype "passive"))
    )
    (net (code "25") (name "Net-(K2-NO)") (class "Default")
      (node (ref "J13") (pin "A1") (pinfunction "1_A1") (pintype "passive"))
      (node (ref "J13") (pin "A2") (pinfunction "1_A2") (pintype "passive"))
      (node (ref "J14") (pin "A1") (pinfunction "1_A1") (pintype "passive"))
      (node (ref "J14") (pin "A2") (pinfunction "1_A2") (pintype "passive"))
      (node (ref "K2") (pin "3") (pinfunction "NO_3") (pintype "bidirectional"))
    )
    (net (code "26") (name "Net-(K3-COIL2)") (class "Default")
      (node (ref "D4") (pin "A") (pinfunction "A_A") (pintype "passive"))
      (node (ref "K3") (pin "1") (pinfunction "COIL2_1") (pintype "bidirectional"))
      (node (ref "LED3") (pin "C") (pinfunction "C_C") (pintype "passive"))
      (node (ref "Q3") (pin "3") (pinfunction "C_3") (pintype "passive"))
    )
    (net (code "27") (name "Net-(K3-NO)") (class "Default")
      (node (ref "J17") (pin "A1") (pinfunction "1_A1") (pintype "passive"))
      (node (ref "J17") (pin "A2") (pinfunction "1_A2") (pintype "passive"))
      (node (ref "J18") (pin "A1") (pinfunction "1_A1") (pintype "passive"))
      (node (ref "J18") (pin "A2") (pinfunction "1_A2") (pintype "passive"))
      (node (ref "K3") (pin "3") (pinfunction "NO_3") (pintype "bidirectional"))
    )
    (net (code "28") (name "Net-(LED1-PadA)") (class "Default")
      (node (ref "LED1") (pin "A") (pinfunction "A_A") (pintype "passive"))
      (node (ref "R9") (pin "1") (pinfunction "1_1") (pintype "passive"))
    )
    (net (code "29") (name "Net-(LED2-PadA)") (class "Default")
      (node (ref "LED2") (pin "A") (pinfunction "A_A") (pintype "passive"))
      (node (ref "R10") (pin "1") (pinfunction "1_1") (pintype "passive"))
    )
    (net (code "30") (name "Net-(LED3-PadA)") (class "Default")
      (node (ref "LED3") (pin "A") (pinfunction "A_A") (pintype "passive"))
      (node (ref "R11") (pin "1") (pinfunction "1_1") (pintype "passive"))
    )
    (net (code "31") (name "Net-(LED4-PadC)") (class "Default")
      (node (ref "LED4") (pin "C") (pinfunction "C_C") (pintype "passive"))
      (node (ref "R12") (pin "2") (pinfunction "2_2") (pintype "passive"))
    )
    (net (code "32") (name "Net-(OK1-A)") (class "Default")
      (node (ref "OK1") (pin "1") (pinfunction "A_1") (pintype "passive"))
      (node (ref "R15") (pin "2") (pinfunction "2_2") (pintype "passive"))
    )
    (net (code "33") (name "Net-(OK1-C)") (class "Default")
      (node (ref "OK1") (pin "2") (pinfunction "C_2") (pintype "passive"))
      (node (ref "Q10") (pin "3") (pinfunction "C_3") (pintype "passive"))
    )
    (net (code "34") (name "Net-(OK2-A)") (class "Default")
      (node (ref "OK2") (pin "1") (pinfunction "A_1") (pintype "passive"))
      (node (ref "R1") (pin "2") (pinfunction "2_2") (pintype "passive"))
    )
    (net (code "35") (name "Net-(OK2-A2)") (class "Default")
      (node (ref "OK2") (pin "6") (pinfunction "A2_6") (pintype "passive"))
      (node (ref "R2") (pin "1") (pinfunction "1_1") (pintype "passive"))
    )
    (net (code "36") (name "Net-(Q1-B)") (class "Default")
      (node (ref "Q1") (pin "1") (pinfunction "B_1") (pintype "passive"))
      (node (ref "Q4") (pin "2") (pinfunction "E_2") (pintype "passive"))
    )
    (net (code "37") (name "Net-(Q2-B)") (class "Default")
      (node (ref "Q2") (pin "1") (pinfunction "B_1") (pintype "passive"))
      (node (ref "Q5") (pin "2") (pinfunction "E_2") (pintype "passive"))
    )
    (net (code "38") (name "Net-(Q3-B)") (class "Default")
      (node (ref "Q3") (pin "1") (pinfunction "B_1") (pintype "passive"))
      (node (ref "Q6") (pin "2") (pinfunction "E_2") (pintype "passive"))
    )
    (net (code "39") (name "Net-(Q4-B)") (class "Default")
      (node (ref "Q4") (pin "1") (pinfunction "B_1") (pintype "passive"))
      (node (ref "R6") (pin "2") (pinfunction "2_2") (pintype "passive"))
    )
    (net (code "40") (name "Net-(Q4-C)") (class "Default")
      (node (ref "Q4") (pin "3") (pinfunction "C_3") (pintype "passive"))
      (node (ref "R3") (pin "1") (pinfunction "1_1") (pintype "passive"))
    )
    (net (code "41") (name "Net-(Q5-B)") (class "Default")
      (node (ref "Q5") (pin "1") (pinfunction "B_1") (pintype "passive"))
      (node (ref "R7") (pin "2") (pinfunction "2_2") (pintype "passive"))
    )
    (net (code "42") (name "Net-(Q5-C)") (class "Default")
      (node (ref "Q5") (pin "3") (pinfunction "C_3") (pintype "passive"))
      (node (ref "R4") (pin "1") (pinfunction "1_1") (pintype "passive"))
    )
    (net (code "43") (name "Net-(Q6-B)") (class "Default")
      (node (ref "Q6") (pin "1") (pinfunction "B_1") (pintype "passive"))
      (node (ref "R8") (pin "2") (pinfunction "2_2") (pintype "passive"))
    )
    (net (code "44") (name "Net-(Q6-C)") (class "Default")
      (node (ref "Q6") (pin "3") (pinfunction "C_3") (pintype "passive"))
      (node (ref "R5") (pin "1") (pinfunction "1_1") (pintype "passive"))
    )
    (net (code "45") (name "Net-(Q8-B)") (class "Default")
      (node (ref "Q8") (pin "1") (pinfunction "B_1") (pintype "passive"))
      (node (ref "Q9") (pin "2") (pinfunction "E_2") (pintype "passive"))
    )
    (net (code "46") (name "Net-(Q8-C)") (class "Default")
      (node (ref "D1") (pin "A") (pinfunction "A_A") (pintype "passive"))
      (node (ref "Q8") (pin "3") (pinfunction "C_3") (pintype "passive"))
      (node (ref "SPK1") (pin "-") (pinfunction "+_-") (pintype "passive"))
    )
    (net (code "47") (name "Net-(Q9-B)") (class "Default")
      (node (ref "Q9") (pin "1") (pinfunction "B_1") (pintype "passive"))
      (node (ref "R28") (pin "2") (pinfunction "2_2") (pintype "passive"))
    )
    (net (code "48") (name "Net-(Q9-C)") (class "Default")
      (node (ref "Q9") (pin "3") (pinfunction "C_3") (pintype "passive"))
      (node (ref "R27") (pin "1") (pinfunction "1_1") (pintype "passive"))
    )
    (net (code "49") (name "Net-(Q10-B)") (class "Default")
      (node (ref "B1") (pin "-") (pinfunction "-_-") (pintype "passive"))
      (node (ref "D5") (pin "C") (pinfunction "C_C") (pintype "passive"))
      (node (ref "Q10") (pin "1") (pinfunction "B_1") (pintype "passive"))
      (node (ref "R22") (pin "1") (pinfunction "1_1") (pintype "passive"))
    )
    (net (code "50") (name "Net-(Q10-E)") (class "Default")
      (node (ref "C6") (pin "2") (pinfunction "2_2") (pintype "passive"))
      (node (ref "D5") (pin "A") (pinfunction "A_A") (pintype "passive"))
      (node (ref "Q10") (pin "2") (pinfunction "E_2") (pintype "passive"))
    )
    (net (code "51") (name "Net-(Q11A-D)") (class "Default")
      (node (ref "J9") (pin "2") (pinfunction "2_2") (pintype "passive"))
      (node (ref "Q11") (pin "D2") (pinfunction "D_D2") (pintype "bidirectional"))
    )
    (net (code "52") (name "Net-(Q11A-G)") (class "Default")
      (node (ref "Q11") (pin "G2") (pinfunction "G_G2") (pintype "bidirectional"))
      (node (ref "Q12") (pin "3") (pinfunction "C_3") (pintype "passive"))
      (node (ref "R32") (pin "1") (pinfunction "1_1") (pintype "passive"))
    )
    (net (code "53") (name "Net-(Q11B-D)") (class "Default")
      (node (ref "J9") (pin "3") (pinfunction "3_3") (pintype "passive"))
      (node (ref "Q11") (pin "D1") (pinfunction "D_D1") (pintype "bidirectional"))
    )
    (net (code "54") (name "Net-(Q11B-G)") (class "Default")
      (node (ref "Q11") (pin "G1") (pinfunction "G_G1") (pintype "bidirectional"))
      (node (ref "Q12") (pin "6") (pinfunction "C_6") (pintype "passive"))
      (node (ref "R31") (pin "1") (pinfunction "1_1") (pintype "passive"))
    )
    (net (code "55") (name "Net-(Q12A-B)") (class "Default")
      (node (ref "Q12") (pin "5") (pinfunction "B_5") (pintype "passive"))
      (node (ref "R34") (pin "1") (pinfunction "1_1") (pintype "passive"))
    )
    (net (code "56") (name "Net-(Q12B-B)") (class "Default")
      (node (ref "Q12") (pin "2") (pinfunction "B_2") (pintype "passive"))
      (node (ref "R33") (pin "1") (pinfunction "1_1") (pintype "passive"))
    )
    (net (code "57") (name "Net-(TR1-A1)") (class "Default")
      (node (ref "C5") (pin "2") (pinfunction "2_2") (pintype "passive"))
      (node (ref "J20") (pin "A1") (pinfunction "1_A1") (pintype "passive"))
      (node (ref "J20") (pin "A2") (pinfunction "1_A2") (pintype "passive"))
      (node (ref "TR1") (pin "1") (pinfunction "A1_1") (pintype "passive"))
    )
    (net (code "58") (name "Net-(TR1-G)") (class "Default")
      (node (ref "R2") (pin "2") (pinfunction "2_2") (pintype "passive"))
      (node (ref "TR1") (pin "3") (pinfunction "G_3") (pintype "passive"))
    )
    (net (code "59") (name "Net-(U2-T+)") (class "Default")
      (node (ref "C3") (pin "2") (pinfunction "2_2") (pintype "passive"))
      (node (ref "FB1") (pin "2") (pinfunction "2_2") (pintype "passive"))
      (node (ref "U2") (pin "3") (pinfunction "T+_3") (pintype "bidirectional"))
    )
    (net (code "60") (name "Net-(U2-T-)") (class "Default")
      (node (ref "C3") (pin "1") (pinfunction "1_1") (pintype "passive"))
      (node (ref "FB2") (pin "2") (pinfunction "2_2") (pintype "passive"))
      (node (ref "U2") (pin "2") (pinfunction "T-_2") (pintype "bidirectional"))
    )
    (net (code "61") (name "Net-(U3-T+)") (class "Default")
      (node (ref "C4") (pin "2") (pinfunction "2_2") (pintype "passive"))
      (node (ref "FB3") (pin "2") (pinfunction "2_2") (pintype "passive"))
      (node (ref "U3") (pin "3") (pinfunction "T+_3") (pintype "bidirectional"))
    )
    (net (code "62") (name "Net-(U3-T-)") (class "Default")
      (node (ref "C4") (pin "1") (pinfunction "1_1") (pintype "passive"))
      (node (ref "FB4") (pin "2") (pinfunction "2_2") (pintype "passive"))
      (node (ref "U3") (pin "2") (pinfunction "T-_2") (pintype "bidirectional"))
    )
    (net (code "63") (name "Net-(U4-AIN0)") (class "Default")
      (node (ref "J6") (pin "3") (pinfunction "3_3") (pintype "passive"))
      (node (ref "U4") (pin "4") (pinfunction "AIN0_4") (pintype "bidirectional"))
    )
    (net (code "64") (name "Net-(U4-SCL)") (class "Default")
      (node (ref "U4") (pin "10") (pinfunction "SCL_10") (pintype "bidirectional"))
      (node (ref "U5") (pin "P$8") (pinfunction "B1_P$8") (pintype "bidirectional"))
    )
    (net (code "65") (name "Net-(U4-SDA)") (class "Default")
      (node (ref "U4") (pin "9") (pinfunction "SDA_9") (pintype "bidirectional"))
      (node (ref "U5") (pin "P$1") (pinfunction "B2_P$1") (pintype "bidirectional"))
    )
    (net (code "66") (name "PA0") (class "Default")
      (node (ref "OK1") (pin "4") (pinfunction "COL_4") (pintype "passive"))
      (node (ref "R14") (pin "1") (pinfunction "1_1") (pintype "passive"))
      (node (ref "U1") (pin "P2$15") (pinfunction "PA0_P2$15") (pintype "bidirectional"))
    )
    (net (code "67") (name "PA1") (class "Default")
      (node (ref "J7") (pin "2") (pinfunction "2_2") (pintype "passive"))
      (node (ref "U1") (pin "P2$14") (pinfunction "PA1_P2$14") (pintype "bidirectional"))
    )
    (net (code "68") (name "PA2") (class "Default")
      (node (ref "J7") (pin "3") (pinfunction "3_3") (pintype "passive"))
      (node (ref "U1") (pin "P2$13") (pinfunction "PA2_P2$13") (pintype "bidirectional"))
    )
    (net (code "69") (name "PA6") (class "Default")
      (node (ref "R34") (pin "2") (pinfunction "2_2") (pintype "passive"))
      (node (ref "U1") (pin "P2$9") (pinfunction "PA6_P2$9") (pintype "bidirectional"))
    )
    (net (code "70") (name "PA8") (class "Default")
      (node (ref "R33") (pin "2") (pinfunction "2_2") (pintype "passive"))
      (node (ref "U1") (pin "P1$5") (pinfunction "PA8_P1$5") (pintype "bidirectional"))
    )
    (net (code "71") (name "PB0") (class "Default")
      (node (ref "J8") (pin "2") (pinfunction "2_2") (pintype "passive"))
      (node (ref "U1") (pin "P2$7") (pinfunction "PB0_P2$7") (pintype "bidirectional"))
    )
    (net (code "72") (name "PB1") (class "Default")
      (node (ref "J8") (pin "1") (pinfunction "1_1") (pintype "passive"))
      (node (ref "U1") (pin "P2$6") (pinfunction "PB1_P2$6") (pintype "bidirectional"))
    )
    (net (code "73") (name "PB2") (class "Default")
      (node (ref "J8") (pin "5") (pinfunction "5_5") (pintype "passive"))
      (node (ref "U1") (pin "P2$5") (pinfunction "PB2_P2$5") (pintype "bidirectional"))
    )
    (net (code "74") (name "PB5") (class "Default")
      (node (ref "R28") (pin "1") (pinfunction "1_1") (pintype "passive"))
      (node (ref "U1") (pin "P1$13") (pinfunction "PB5_P1$13") (pintype "bidirectional"))
    )
    (net (code "75") (name "PB8") (class "Default")
      (node (ref "R1") (pin "1") (pinfunction "1_1") (pintype "passive"))
      (node (ref "U1") (pin "P1$16") (pinfunction "PB8_P1$16") (pintype "bidirectional"))
    )
    (net (code "76") (name "PC13") (class "Default")
      (node (ref "R8") (pin "1") (pinfunction "1_1") (pintype "passive"))
      (node (ref "U1") (pin "P2$19") (pinfunction "PC13_P2$19") (pintype "bidirectional"))
    )
    (net (code "77") (name "PC14") (class "Default")
      (node (ref "R7") (pin "1") (pinfunction "1_1") (pintype "passive"))
      (node (ref "U1") (pin "P2$18") (pinfunction "PC14_P2$18") (pintype "bidirectional"))
    )
    (net (code "78") (name "PC15") (class "Default")
      (node (ref "R6") (pin "1") (pinfunction "1_1") (pintype "passive"))
      (node (ref "U1") (pin "P2$17") (pinfunction "PC15_P2$17") (pintype "bidirectional"))
    )
    (net (code "79") (name "RTS") (class "Default")
      (node (ref "C14") (pin "1") (pinfunction "1_1") (pintype "passive"))
      (node (ref "J27") (pin "5") (pinfunction "5_5") (pintype "passive"))
      (node (ref "R30") (pin "2") (pinfunction "2_2") (pintype "passive"))
    )
    (net (code "80") (name "SPI1_MISO") (class "Default")
      (node (ref "J24") (pin "7") (pinfunction "DAT0_7") (pintype "bidirectional"))
      (node (ref "U1") (pin "P1$12") (pinfunction "PB4_P1$12") (pintype "bidirectional"))
    )
    (net (code "81") (name "SPI1_MOSI") (class "Default")
      (node (ref "J24") (pin "3") (pinfunction "CMD_3") (pintype "passive"))
      (node (ref "U1") (pin "P2$8") (pinfunction "PA7_P2$8") (pintype "bidirectional"))
    )
    (net (code "82") (name "SPI1_NSS") (class "Default")
      (node (ref "J24") (pin "2") (pinfunction "CD/DAT3_2") (pintype "passive"))
      (node (ref "U1") (pin "P2$11") (pinfunction "PA4_P2$11") (pintype "bidirectional"))
    )
    (net (code "83") (name "SPI1_SCK") (class "Default")
      (node (ref "J24") (pin "5") (pinfunction "CLK_5") (pintype "passive"))
      (node (ref "U1") (pin "P2$10") (pinfunction "PA5_P2$10") (pintype "bidirectional"))
    )
    (net (code "84") (name "SPI2_MISO") (class "Default")
      (node (ref "U1") (pin "P1$3") (pinfunction "PB14_P1$3") (pintype "bidirectional"))
      (node (ref "U2") (pin "7") (pinfunction "(MI)SO_7") (pintype "bidirectional"))
      (node (ref "U3") (pin "7") (pinfunction "(MI)SO_7") (pintype "bidirectional"))
    )
    (net (code "85") (name "SPI2_NSS") (class "Default")
      (node (ref "U1") (pin "P1$1") (pinfunction "PB12_P1$1") (pintype "bidirectional"))
      (node (ref "U2") (pin "6") (pinfunction "~{CS}_6") (pintype "bidirectional"))
    )
    (net (code "86") (name "SPI2_NSS2") (class "Default")
      (node (ref "U1") (pin "P1$17") (pinfunction "PB9_P1$17") (pintype "bidirectional"))
      (node (ref "U3") (pin "6") (pinfunction "~{CS}_6") (pintype "bidirectional"))
    )
    (net (code "87") (name "SPI2_SCK") (class "Default")
      (node (ref "U1") (pin "P1$2") (pinfunction "PB13_P1$2") (pintype "bidirectional"))
      (node (ref "U2") (pin "5") (pinfunction "SCK_5") (pintype "bidirectional"))
      (node (ref "U3") (pin "5") (pinfunction "SCK_5") (pintype "bidirectional"))
    )
    (net (code "88") (name "UART1_RX") (class "Default")
      (node (ref "J27") (pin "3") (pinfunction "3_3") (pintype "passive"))
      (node (ref "U1") (pin "P1$7") (pinfunction "PA10_P1$7") (pintype "bidirectional"))
    )
    (net (code "89") (name "UART1_TX") (class "Default")
      (node (ref "J27") (pin "2") (pinfunction "2_2") (pintype "passive"))
      (node (ref "U1") (pin "P1$6") (pinfunction "PA9_P1$6") (pintype "bidirectional"))
    )
    (net (code "90") (name "UART6_5V_RX") (class "Default")
      (node (ref "J1") (pin "2") (pinfunction "2_2") (pintype "passive"))
      (node (ref "Q7") (pin "3") (pinfunction "D_3") (pintype "bidirectional"))
      (node (ref "R16") (pin "1") (pinfunction "1_1") (pintype "passive"))
      (node (ref "SJ2") (pin "2") (pinfunction "2_2") (pintype "passive"))
    )
    (net (code "91") (name "UART6_5V_TX") (class "Default")
      (node (ref "J1") (pin "3") (pinfunction "3_3") (pintype "passive"))
      (node (ref "Q7") (pin "6") (pinfunction "D_6") (pintype "bidirectional"))
      (node (ref "R17") (pin "1") (pinfunction "1_1") (pintype "passive"))
      (node (ref "SJ1") (pin "2") (pinfunction "2_2") (pintype "passive"))
    )
    (net (code "92") (name "UART6_RX") (class "Default")
      (node (ref "Q7") (pin "4") (pinfunction "S_4") (pintype "bidirectional"))
      (node (ref "R18") (pin "1") (pinfunction "1_1") (pintype "passive"))
      (node (ref "SJ2") (pin "1") (pinfunction "1_1") (pintype "passive"))
      (node (ref "U1") (pin "P1$9") (pinfunction "PA12_P1$9") (pintype "bidirectional"))
    )
    (net (code "93") (name "UART6_TX") (class "Default")
      (node (ref "Q7") (pin "1") (pinfunction "S_1") (pintype "bidirectional"))
      (node (ref "R19") (pin "1") (pinfunction "1_1") (pintype "passive"))
      (node (ref "SJ1") (pin "1") (pinfunction "1_1") (pintype "passive"))
      (node (ref "U1") (pin "P1$8") (pinfunction "PA11_P1$8") (pintype "bidirectional"))
    )
    (net (code "94") (name "unconnected-(F1-Pad1B)") (class "Default")
      (node (ref "F1") (pin "1B") (pinfunction "1B_1B") (pintype "passive"))
    )
    (net (code "95") (name "unconnected-(F1-Pad2B)") (class "Default")
      (node (ref "F1") (pin "2B") (pinfunction "2B_2B") (pintype "passive"))
    )
    (net (code "96") (name "unconnected-(J24-DAT1-Pad8)") (class "Default")
      (node (ref "J24") (pin "8") (pinfunction "DAT1_8") (pintype "bidirectional"))
    )
    (net (code "97") (name "unconnected-(J24-DAT2-Pad1)") (class "Default")
      (node (ref "J24") (pin "1") (pinfunction "DAT2_1") (pintype "bidirectional"))
    )
    (net (code "98") (name "unconnected-(J24-DETECT_LEVEL-Pad9)") (class "Default")
      (node (ref "J24") (pin "9") (pinfunction "DETECT_LEVEL_9") (pintype "passive"))
    )
    (net (code "99") (name "unconnected-(J24-DETECT_SWITCH-Pad10)") (class "Default")
      (node (ref "J24") (pin "10") (pinfunction "DETECT_SWITCH_10") (pintype "passive"))
    )
    (net (code "100") (name "unconnected-(U1-PA3-PadP2$12)") (class "Default")
      (node (ref "U1") (pin "P2$12") (pinfunction "PA3_P2$12") (pintype "bidirectional"))
    )
    (net (code "101") (name "unconnected-(U1-PA15-PadP1$10)") (class "Default")
      (node (ref "U1") (pin "P1$10") (pinfunction "PA15_P1$10") (pintype "bidirectional"))
    )
    (net (code "102") (name "unconnected-(U1-PB15-PadP1$4)") (class "Default")
      (node (ref "U1") (pin "P1$4") (pinfunction "PB15_P1$4") (pintype "bidirectional"))
    )
    (net (code "103") (name "unconnected-(U1-VB-PadP2$20)") (class "Default")
      (node (ref "U1") (pin "P2$20") (pinfunction "VB_P2$20") (pintype "bidirectional"))
    )
    (net (code "104") (name "unconnected-(U4-ALERT-Pad2)") (class "Default")
      (node (ref "U4") (pin "2") (pinfunction "ALERT_2") (pintype "bidirectional"))
    )
  )
)
